# POWER.net
KiCad netlist of a schematic drawn in Altium Designer
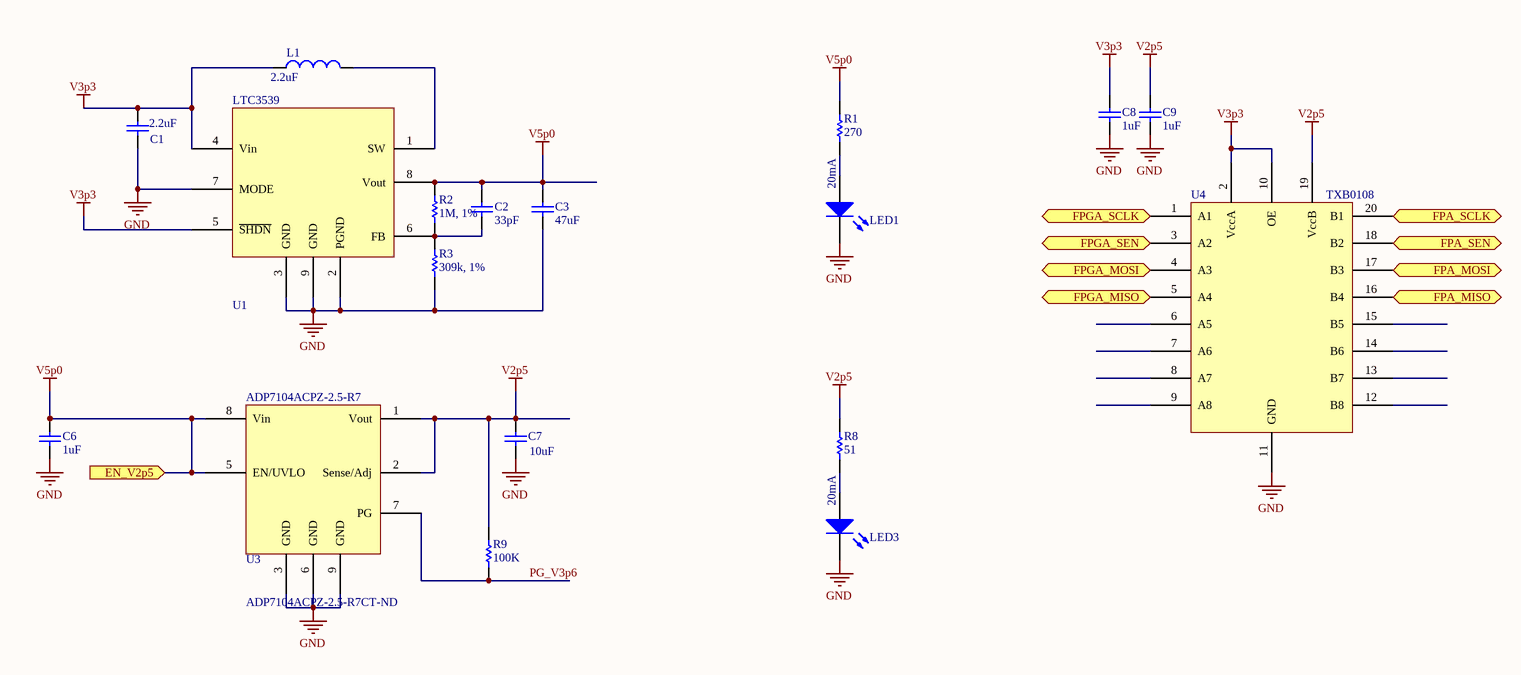
[diagram p0: POWER.SchDoc]

(export (version "E")
  (design (tool "Eeschema 10.0.6"))
  (components
    (comp (ref "C1")
      (value "2.2uF")
      (footprint "CAPC1206(3216)170_N")
      (fields (field (name "Comment") "587-1329-2-ND"))
      (libsource (lib "Components") (part "CAP, 1206, 2.2uF"))
    )
    (comp (ref "C2")
      (value "33pF")
      (footprint "CAPC01005(0402)22_N")
      (fields (field (name "Comment") "CAP, 0402, 33pF"))
      (libsource (lib "Components") (part "CAP, 0402, 33pF"))
    )
    (comp (ref "C3")
      (value "47uF")
      (footprint "CAPC1206(3216)170_N")
      (fields (field (name "Comment") "CAP, 1206, 47uF"))
      (libsource (lib "Components") (part "CAP, 1206, 47uF"))
    )
    (comp (ref "C6")
      (value "1uF")
      (footprint "CAPC01005(0402)22_N")
      (fields (field (name "Comment") "CAP, 0402, 1uF"))
      (libsource (lib "Components") (part "CAP, 0402, 1uF"))
    )
    (comp (ref "C7")
      (value "10uF")
      (footprint "CAPC0805(2012)130_N")
      (fields (field (name "Comment") "CAP, 0805, 10uF"))
      (libsource (lib "Components") (part "CAP, 0805, 10uF"))
    )
    (comp (ref "C8")
      (value "1uF")
      (footprint "CAPC01005(0402)22_N")
      (fields (field (name "Comment") "CAP, 0402, 1uF"))
      (libsource (lib "Components") (part "CAP, 0402, 1uF"))
    )
    (comp (ref "C9")
      (value "1uF")
      (footprint "CAPC01005(0402)22_N")
      (fields (field (name "Comment") "CAP, 0402, 1uF"))
      (libsource (lib "Components") (part "CAP, 0402, 1uF"))
    )
    (comp (ref "L1")
      (value "2.2uF")
      (footprint "INDUCTOR, SMD, TDK")
      (fields (field (name "Comment") "INDUCTOR, SMD, 2.2uF"))
      (libsource (lib "Components") (part "INDUCTOR, SMD, 2.2uF"))
    )
    (comp (ref "LED1")
      (value "LED, GREEN, 0603, LITE-ON")
      (footprint "0603, LED")
      (libsource (lib "Components") (part "LED, GREEN, 0603, LITE-ON"))
    )
    (comp (ref "LED3")
      (value "LED, GREEN, 0603, LITE-ON")
      (footprint "0603, LED")
      (libsource (lib "Components") (part "LED, GREEN, 0603, LITE-ON"))
    )
    (comp (ref "R1")
      (value "270")
      (footprint "RES, 0603")
      (description "Resistor, 0603, 1/10W, 270 ohm")
      (fields
        (field (name "MANUFACTURER") "Panasonic Electronic Components")
        (field (name "MANUFACTURER PART NUMBER") "ERJ-3EKF2700V")
      )
      (libsource (lib "Resistors0603") (part "RES_0603_270"))
    )
    (comp (ref "R2")
      (value "1M, 1%")
      (footprint "RESC0402(1005)_N")
      (fields (field (name "Comment") "RES, 0402, 1M, 1%"))
      (libsource (lib "Components") (part "RES, 0402, 1M, 1%"))
    )
    (comp (ref "R3")
      (value "309k, 1%")
      (footprint "RESC0402(1005)_N")
      (fields (field (name "Comment") "RES, 0402, 309k, 1%"))
      (libsource (lib "Components") (part "RES, 0402, 309k, 1%"))
    )
    (comp (ref "R8")
      (value "51")
      (footprint "RES, 0603")
      (description "Resistor, 0603, 1/10W, 51 ohm")
      (fields
        (field (name "MANUFACTURER") "Panasonic Electronic Components")
        (field (name "MANUFACTURER PART NUMBER") "ERJ-3EKF51R0V")
      )
      (libsource (lib "Resistors0603") (part "RES_0603_51"))
    )
    (comp (ref "R9")
      (value "100K")
      (footprint "RES, 0603")
      (description "Resistor, 0603, 1/10W, 100K ohm")
      (fields
        (field (name "MANUFACTURER") "Panasonic Electronic Components")
        (field (name "MANUFACTURER PART NUMBER") "ERJ-3EKF1003V")
      )
      (libsource (lib "Resistors0603") (part "RES_0603_100K"))
    )
    (comp (ref "U1")
      (value "LTC3539")
      (footprint "QFN45P300X200X80-8N")
      (description "2A, 1MHz/2MHz Synchronous Step-Up DC/DC Converters")
      (libsource (lib "Components") (part "LTC3539"))
    )
    (comp (ref "U3")
      (value "ADP7104ACPZ-2.5-R7")
      (footprint "QFN50P300X300X75-8N")
      (description "2.5V Voltage Regulator")
      (fields (field (name "SUPPLIER PART NUMBER 1") "ADP7104ACPZ-2.5-R7CT-ND"))
      (libsource (lib "Components") (part "ADP7104ACPZ-2.5-R7"))
    )
    (comp (ref "U4")
      (value "TXB0108")
      (footprint "TSOP65P640X120-20N")
      (libsource (lib "Components") (part "TXB0108; 8-bit Bi-Directional Voltage Translator"))
    )
  )
  (nets
    (net (code "1") (name "/FPA_MISO") (class "Default")
      (node (ref "U4") (pin "16") (pinfunction "B4_16") (pintype "passive"))
    )
    (net (code "2") (name "/FPA_MOSI") (class "Default")
      (node (ref "U4") (pin "17") (pinfunction "B3_17") (pintype "passive"))
    )
    (net (code "3") (name "/FPA_SCLK") (class "Default")
      (node (ref "U4") (pin "20") (pinfunction "B1_20") (pintype "passive"))
    )
    (net (code "4") (name "/FPA_SEN") (class "Default")
      (node (ref "U4") (pin "18") (pinfunction "B2_18") (pintype "passive"))
    )
    (net (code "5") (name "/FPGA_MISO") (class "Default")
      (node (ref "U4") (pin "5") (pinfunction "A4_5") (pintype "passive"))
    )
    (net (code "6") (name "/FPGA_MOSI") (class "Default")
      (node (ref "U4") (pin "4") (pinfunction "A3_4") (pintype "passive"))
    )
    (net (code "7") (name "/FPGA_SCLK") (class "Default")
      (node (ref "U4") (pin "1") (pinfunction "A1_1") (pintype "passive"))
    )
    (net (code "8") (name "/FPGA_SEN") (class "Default")
      (node (ref "U4") (pin "3") (pinfunction "A2_3") (pintype "passive"))
    )
    (net (code "9") (name "/PG_V3p6") (class "Default")
      (node (ref "R9") (pin "1") (pinfunction "1_1") (pintype "passive"))
      (node (ref "U3") (pin "7") (pinfunction "PG_7") (pintype "passive"))
    )
    (net (code "10") (name "GND") (class "Default")
      (node (ref "C1") (pin "1") (pinfunction "1_1") (pintype "passive"))
      (node (ref "C3") (pin "1") (pinfunction "1_1") (pintype "passive"))
      (node (ref "C6") (pin "1") (pinfunction "1_1") (pintype "passive"))
      (node (ref "C7") (pin "1") (pinfunction "1_1") (pintype "passive"))
      (node (ref "C8") (pin "1") (pinfunction "1_1") (pintype "passive"))
      (node (ref "C9") (pin "1") (pinfunction "1_1") (pintype "passive"))
      (node (ref "LED1") (pin "1") (pinfunction "C_1") (pintype "passive"))
      (node (ref "LED3") (pin "1") (pinfunction "C_1") (pintype "passive"))
      (node (ref "R3") (pin "1") (pinfunction "1_1") (pintype "passive"))
      (node (ref "U1") (pin "2") (pinfunction "PGND_2") (pintype "passive"))
      (node (ref "U1") (pin "3") (pinfunction "GND_3") (pintype "passive"))
      (node (ref "U1") (pin "7") (pinfunction "MODE_7") (pintype "passive"))
      (node (ref "U1") (pin "9") (pinfunction "GND_9") (pintype "passive"))
      (node (ref "U3") (pin "3") (pinfunction "GND_3") (pintype "passive"))
      (node (ref "U3") (pin "6") (pinfunction "GND_6") (pintype "passive"))
      (node (ref "U3") (pin "9") (pinfunction "GND_9") (pintype "passive"))
      (node (ref "U4") (pin "11") (pinfunction "GND_11") (pintype "passive"))
    )
    (net (code "11") (name "Net-(LED1-A)") (class "Default")
      (node (ref "LED1") (pin "2") (pinfunction "A_2") (pintype "passive"))
      (node (ref "R1") (pin "1") (pinfunction "1_1") (pintype "passive"))
    )
    (net (code "12") (name "Net-(LED3-A)") (class "Default")
      (node (ref "LED3") (pin "2") (pinfunction "A_2") (pintype "passive"))
      (node (ref "R8") (pin "1") (pinfunction "1_1") (pintype "passive"))
    )
    (net (code "13") (name "Net-(U1-FB)") (class "Default")
      (node (ref "C2") (pin "1") (pinfunction "1_1") (pintype "passive"))
      (node (ref "R2") (pin "1") (pinfunction "1_1") (pintype "passive"))
      (node (ref "R3") (pin "2") (pinfunction "2_2") (pintype "passive"))
      (node (ref "U1") (pin "6") (pinfunction "FB_6") (pintype "passive"))
    )
    (net (code "14") (name "Net-(U1-SW)") (class "Default")
      (node (ref "L1") (pin "2") (pinfunction "2_2") (pintype "passive"))
      (node (ref "U1") (pin "1") (pinfunction "SW_1") (pintype "passive"))
    )
    (net (code "15") (name "V2p5") (class "Default")
      (node (ref "C7") (pin "2") (pinfunction "2_2") (pintype "passive"))
      (node (ref "C9") (pin "2") (pinfunction "2_2") (pintype "passive"))
      (node (ref "R8") (pin "2") (pinfunction "2_2") (pintype "passive"))
      (node (ref "R9") (pin "2") (pinfunction "2_2") (pintype "passive"))
      (node (ref "U3") (pin "1") (pinfunction "Vout_1") (pintype "passive"))
      (node (ref "U3") (pin "2") (pinfunction "Sense/Adj_2") (pintype "passive"))
      (node (ref "U4") (pin "19") (pinfunction "VccB_19") (pintype "passive"))
    )
    (net (code "16") (name "V3p3") (class "Default")
      (node (ref "C1") (pin "2") (pinfunction "2_2") (pintype "passive"))
      (node (ref "C8") (pin "2") (pinfunction "2_2") (pintype "passive"))
      (node (ref "L1") (pin "1") (pinfunction "1_1") (pintype "passive"))
      (node (ref "U1") (pin "4") (pinfunction "Vin_4") (pintype "passive"))
      (node (ref "U1") (pin "5") (pinfunction "~{SHDN}_5") (pintype "passive"))
      (node (ref "U4") (pin "10") (pinfunction "OE_10") (pintype "passive"))
      (node (ref "U4") (pin "2") (pinfunction "VccA_2") (pintype "passive"))
    )
    (net (code "17") (name "V5p0") (class "Default")
      (node (ref "C2") (pin "2") (pinfunction "2_2") (pintype "passive"))
      (node (ref "C3") (pin "2") (pinfunction "2_2") (pintype "passive"))
      (node (ref "C6") (pin "2") (pinfunction "2_2") (pintype "passive"))
      (node (ref "R1") (pin "2") (pinfunction "2_2") (pintype "passive"))
      (node (ref "R2") (pin "2") (pinfunction "2_2") (pintype "passive"))
      (node (ref "U1") (pin "8") (pinfunction "Vout_8") (pintype "passive"))
      (node (ref "U3") (pin "5") (pinfunction "EN/UVLO_5") (pintype "passive"))
      (node (ref "U3") (pin "8") (pinfunction "Vin_8") (pintype "passive"))
    )
    (net (code "18") (name "unconnected-(U4-A5-Pad6)") (class "Default")
      (node (ref "U4") (pin "6") (pinfunction "A5_6") (pintype "passive"))
    )
    (net (code "19") (name "unconnected-(U4-A6-Pad7)") (class "Default")
      (node (ref "U4") (pin "7") (pinfunction "A6_7") (pintype "passive"))
    )
    (net (code "20") (name "unconnected-(U4-A7-Pad8)") (class "Default")
      (node (ref "U4") (pin "8") (pinfunction "A7_8") (pintype "passive"))
    )
    (net (code "21") (name "unconnected-(U4-A8-Pad9)") (class "Default")
      (node (ref "U4") (pin "9") (pinfunction "A8_9") (pintype "passive"))
    )
    (net (code "22") (name "unconnected-(U4-B5-Pad15)") (class "Default")
      (node (ref "U4") (pin "15") (pinfunction "B5_15") (pintype "passive"))
    )
    (net (code "23") (name "unconnected-(U4-B6-Pad14)") (class "Default")
      (node (ref "U4") (pin "14") (pinfunction "B6_14") (pintype "passive"))
    )
    (net (code "24") (name "unconnected-(U4-B7-Pad13)") (class "Default")
      (node (ref "U4") (pin "13") (pinfunction "B7_13") (pintype "passive"))
    )
    (net (code "25") (name "unconnected-(U4-B8-Pad12)") (class "Default")
      (node (ref "U4") (pin "12") (pinfunction "B8_12") (pintype "passive"))
    )
  )
)
